# FAJAS_EDCPSU_USBC.net
KiCad netlist of a schematic drawn in EAGLE
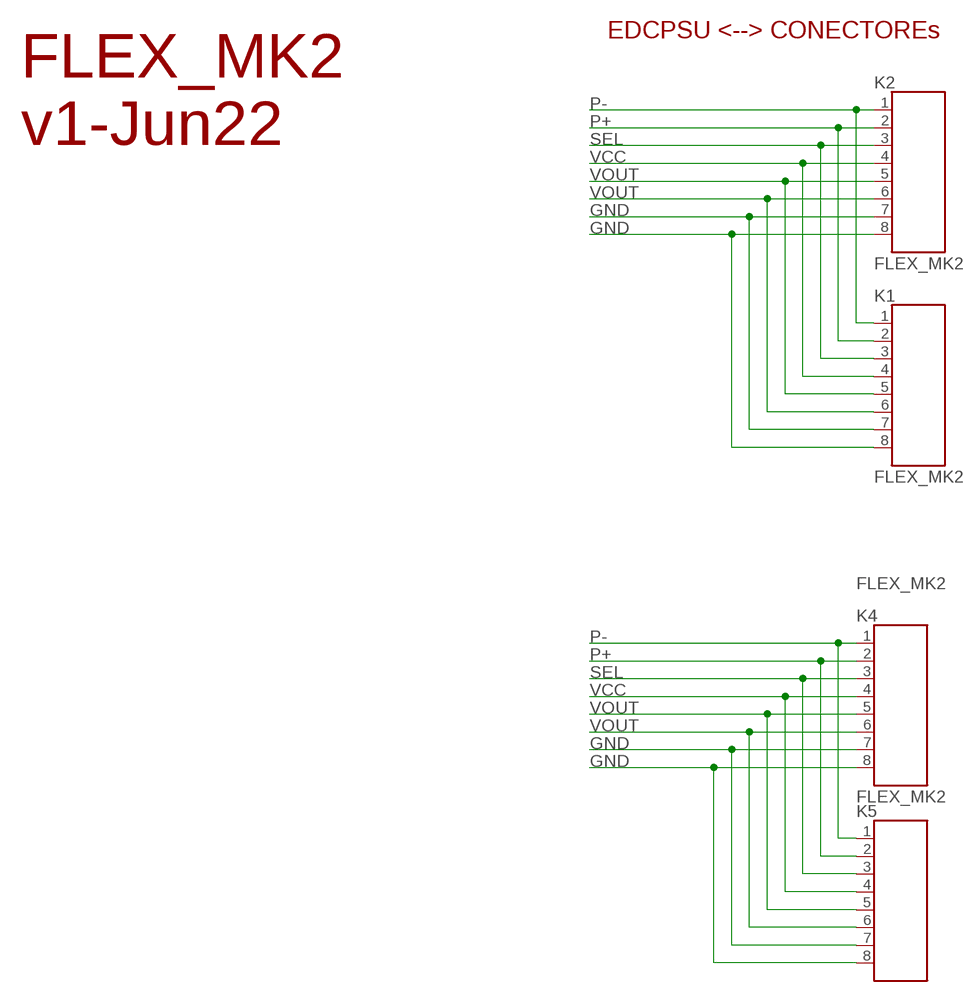
[diagram p0: schematic, sheet 1]

(export (version "E")
  (design (tool "Eeschema 10.0.6"))
  (components
    (comp (ref "K1")
      (value "FLEX_MK2")
      (footprint "eagle-import:FLEX8")
      (libsource (lib "eagle-import") (part "FLEX8"))
    )
    (comp (ref "K2")
      (value "FLEX_MK2")
      (footprint "eagle-import:FLEX8")
      (libsource (lib "eagle-import") (part "FLEX8"))
    )
    (comp (ref "K4")
      (value "FLEX_MK2")
      (footprint "eagle-import:FLEX8")
      (libsource (lib "eagle-import") (part "FLEX8"))
    )
    (comp (ref "K5")
      (value "FLEX_MK2")
      (footprint "eagle-import:FLEX8")
      (libsource (lib "eagle-import") (part "FLEX8"))
    )
  )
  (nets
    (net (code "1") (name "/GND") (class "Default")
      (node (ref "K1") (pin "7") (pinfunction "7_7") (pintype "passive"))
      (node (ref "K1") (pin "8") (pinfunction "8_8") (pintype "passive"))
      (node (ref "K2") (pin "7") (pinfunction "7_7") (pintype "passive"))
      (node (ref "K2") (pin "8") (pinfunction "8_8") (pintype "passive"))
      (node (ref "K4") (pin "7") (pinfunction "7_7") (pintype "passive"))
      (node (ref "K4") (pin "8") (pinfunction "8_8") (pintype "passive"))
      (node (ref "K5") (pin "7") (pinfunction "7_7") (pintype "passive"))
      (node (ref "K5") (pin "8") (pinfunction "8_8") (pintype "passive"))
    )
    (net (code "2") (name "/P+") (class "Default")
      (node (ref "K1") (pin "2") (pinfunction "2_2") (pintype "passive"))
      (node (ref "K2") (pin "2") (pinfunction "2_2") (pintype "passive"))
      (node (ref "K4") (pin "2") (pinfunction "2_2") (pintype "passive"))
      (node (ref "K5") (pin "2") (pinfunction "2_2") (pintype "passive"))
    )
    (net (code "3") (name "/P-") (class "Default")
      (node (ref "K1") (pin "1") (pinfunction "1_1") (pintype "passive"))
      (node (ref "K2") (pin "1") (pinfunction "1_1") (pintype "passive"))
      (node (ref "K4") (pin "1") (pinfunction "1_1") (pintype "passive"))
      (node (ref "K5") (pin "1") (pinfunction "1_1") (pintype "passive"))
    )
    (net (code "4") (name "/SEL") (class "Default")
      (node (ref "K1") (pin "3") (pinfunction "3_3") (pintype "passive"))
      (node (ref "K2") (pin "3") (pinfunction "3_3") (pintype "passive"))
      (node (ref "K4") (pin "3") (pinfunction "3_3") (pintype "passive"))
      (node (ref "K5") (pin "3") (pinfunction "3_3") (pintype "passive"))
    )
    (net (code "5") (name "/VCC") (class "Default")
      (node (ref "K1") (pin "4") (pinfunction "4_4") (pintype "passive"))
      (node (ref "K2") (pin "4") (pinfunction "4_4") (pintype "passive"))
      (node (ref "K4") (pin "4") (pinfunction "4_4") (pintype "passive"))
      (node (ref "K5") (pin "4") (pinfunction "4_4") (pintype "passive"))
    )
    (net (code "6") (name "/VOUT") (class "Default")
      (node (ref "K1") (pin "5") (pinfunction "5_5") (pintype "passive"))
      (node (ref "K1") (pin "6") (pinfunction "6_6") (pintype "passive"))
      (node (ref "K2") (pin "5") (pinfunction "5_5") (pintype "passive"))
      (node (ref "K2") (pin "6") (pinfunction "6_6") (pintype "passive"))
      (node (ref "K4") (pin "5") (pinfunction "5_5") (pintype "passive"))
      (node (ref "K4") (pin "6") (pinfunction "6_6") (pintype "passive"))
      (node (ref "K5") (pin "5") (pinfunction "5_5") (pintype "passive"))
      (node (ref "K5") (pin "6") (pinfunction "6_6") (pintype "passive"))
    )
  )
)
